# 6_mpu6050.net
KiCad netlist of a schematic drawn in Altium Designer
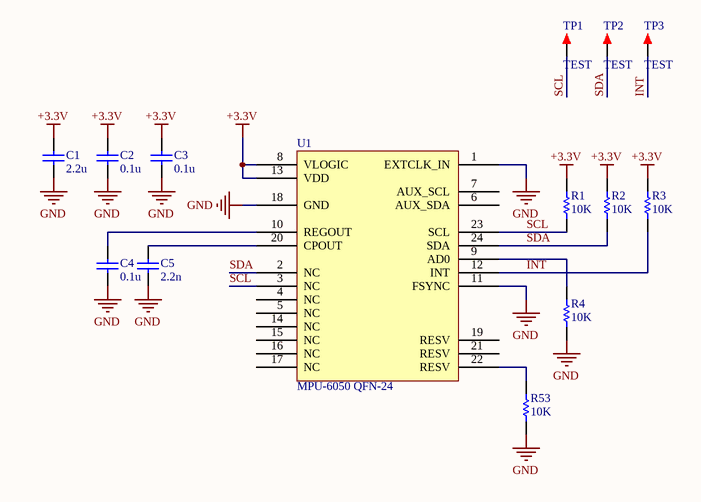
[diagram p0: 6_mpu6050.SchDoc]

(export (version "E")
  (design (tool "Eeschema 10.0.6"))
  (components
    (comp (ref "C1")
      (value "2.2u")
      (footprint "CAP_0603_SMD")
      (description "Capacitor, 0603, SMD")
      (fields (field (name "PUBLISHER") "Altium Limited"))
      (libsource (lib "myRLC") (part "CAP_0603_SMD"))
    )
    (comp (ref "C2")
      (value "0.1u")
      (footprint "CAP_0603_SMD")
      (description "Capacitor, 0603, SMD")
      (fields (field (name "PUBLISHER") "Altium Limited"))
      (libsource (lib "myRLC") (part "CAP_0603_SMD"))
    )
    (comp (ref "C3")
      (value "0.1u")
      (footprint "CAP_0603_SMD")
      (description "Capacitor, 0603, SMD")
      (fields (field (name "PUBLISHER") "Altium Limited"))
      (libsource (lib "myRLC") (part "CAP_0603_SMD"))
    )
    (comp (ref "C4")
      (value "0.1u")
      (footprint "CAP_0603_SMD")
      (description "Capacitor, 0603, SMD")
      (fields (field (name "PUBLISHER") "Altium Limited"))
      (libsource (lib "myRLC") (part "CAP_0603_SMD"))
    )
    (comp (ref "C5")
      (value "2.2n")
      (footprint "CAP_0603_SMD")
      (description "Capacitor, 0603, SMD")
      (fields (field (name "PUBLISHER") "Altium Limited"))
      (libsource (lib "myRLC") (part "CAP_0603_SMD"))
    )
    (comp (ref "R1")
      (value "10K")
      (footprint "RES_0603_SMD")
      (description "Resistor, 0603, SMD")
      (fields (field (name "PUBLISHER") "Altium Limited"))
      (libsource (lib "myRLC") (part "RES_0603_SMD"))
    )
    (comp (ref "R2")
      (value "10K")
      (footprint "RES_0603_SMD")
      (description "Resistor, 0603, SMD")
      (fields (field (name "PUBLISHER") "Altium Limited"))
      (libsource (lib "myRLC") (part "RES_0603_SMD"))
    )
    (comp (ref "R3")
      (value "10K")
      (footprint "RES_0603_SMD")
      (description "Resistor, 0603, SMD")
      (fields (field (name "PUBLISHER") "Altium Limited"))
      (libsource (lib "myRLC") (part "RES_0603_SMD"))
    )
    (comp (ref "R4")
      (value "10K")
      (footprint "RES_0603_SMD")
      (description "Resistor, 0603, SMD")
      (fields (field (name "PUBLISHER") "Altium Limited"))
      (libsource (lib "myRLC") (part "RES_0603_SMD"))
    )
    (comp (ref "R53")
      (value "10K")
      (footprint "RES_0603_SMD")
      (description "Resistor, 0603, SMD")
      (fields (field (name "PUBLISHER") "Altium Limited"))
      (libsource (lib "myRLC") (part "RES_0603_SMD"))
    )
    (comp (ref "TP1")
      (value "TEST")
      (footprint "TEST 1.2")
      (description "测试点")
      (libsource (lib "0.7 - 常用按键-开关-蜂鸣器-电池-测试点") (part "TEST"))
    )
    (comp (ref "TP2")
      (value "TEST")
      (footprint "TEST 1.2")
      (description "测试点")
      (libsource (lib "0.7 - 常用按键-开关-蜂鸣器-电池-测试点") (part "TEST"))
    )
    (comp (ref "TP3")
      (value "TEST")
      (footprint "TEST 1.2")
      (description "测试点")
      (libsource (lib "0.7 - 常用按键-开关-蜂鸣器-电池-测试点") (part "TEST"))
    )
    (comp (ref "U1")
      (value "MPU-6050 QFN-24")
      (footprint "IC_QFN-24_4x4_NoExposedPad")
      (description "Triple Axis Accelerometer and Gyro")
      (libsource (lib "myICs") (part "MPU-6050 QFN24 4x4"))
    )
  )
  (nets
    (net (code "1") (name "+3.3V") (class "Default")
      (node (ref "C1") (pin "2") (pinfunction "2_2") (pintype "passive"))
      (node (ref "C2") (pin "2") (pinfunction "2_2") (pintype "passive"))
      (node (ref "C3") (pin "2") (pinfunction "2_2") (pintype "passive"))
      (node (ref "R1") (pin "2") (pinfunction "2_2") (pintype "passive"))
      (node (ref "R2") (pin "2") (pinfunction "2_2") (pintype "passive"))
      (node (ref "R3") (pin "2") (pinfunction "2_2") (pintype "passive"))
      (node (ref "U1") (pin "13") (pinfunction "VDD_13") (pintype "passive"))
      (node (ref "U1") (pin "8") (pinfunction "VLOGIC_8") (pintype "passive"))
    )
    (net (code "2") (name "/INT") (class "Default")
      (node (ref "R3") (pin "1") (pinfunction "1_1") (pintype "passive"))
      (node (ref "TP3") (pin "1") (pinfunction "1_1") (pintype "passive"))
      (node (ref "U1") (pin "12") (pinfunction "INT_12") (pintype "passive"))
    )
    (net (code "3") (name "/SCL") (class "Default")
      (node (ref "R1") (pin "1") (pinfunction "1_1") (pintype "passive"))
      (node (ref "TP1") (pin "1") (pinfunction "1_1") (pintype "passive"))
      (node (ref "U1") (pin "23") (pinfunction "SCL_23") (pintype "passive"))
      (node (ref "U1") (pin "3") (pinfunction "NC_3") (pintype "passive"))
    )
    (net (code "4") (name "/SDA") (class "Default")
      (node (ref "R2") (pin "1") (pinfunction "1_1") (pintype "passive"))
      (node (ref "TP2") (pin "1") (pinfunction "1_1") (pintype "passive"))
      (node (ref "U1") (pin "2") (pinfunction "NC_2") (pintype "passive"))
      (node (ref "U1") (pin "24") (pinfunction "SDA_24") (pintype "passive"))
    )
    (net (code "5") (name "GND") (class "Default")
      (node (ref "C1") (pin "1") (pinfunction "1_1") (pintype "passive"))
      (node (ref "C2") (pin "1") (pinfunction "1_1") (pintype "passive"))
      (node (ref "C3") (pin "1") (pinfunction "1_1") (pintype "passive"))
      (node (ref "C4") (pin "2") (pinfunction "2_2") (pintype "passive"))
      (node (ref "C5") (pin "2") (pinfunction "2_2") (pintype "passive"))
      (node (ref "R4") (pin "1") (pinfunction "1_1") (pintype "passive"))
      (node (ref "R53") (pin "1") (pinfunction "1_1") (pintype "passive"))
      (node (ref "U1") (pin "1") (pinfunction "EXTCLK_IN_1") (pintype "passive"))
      (node (ref "U1") (pin "11") (pinfunction "FSYNC_11") (pintype "passive"))
      (node (ref "U1") (pin "18") (pinfunction "GND_18") (pintype "passive"))
    )
    (net (code "6") (name "Net-(R53-Pad2)") (class "Default")
      (node (ref "R53") (pin "2") (pinfunction "2_2") (pintype "passive"))
      (node (ref "U1") (pin "22") (pinfunction "RESV_22") (pintype "passive"))
    )
    (net (code "7") (name "Net-(U1-AD0)") (class "Default")
      (node (ref "R4") (pin "2") (pinfunction "2_2") (pintype "passive"))
      (node (ref "U1") (pin "9") (pinfunction "AD0_9") (pintype "passive"))
    )
    (net (code "8") (name "Net-(U1-CPOUT)") (class "Default")
      (node (ref "C5") (pin "1") (pinfunction "1_1") (pintype "passive"))
      (node (ref "U1") (pin "20") (pinfunction "CPOUT_20") (pintype "passive"))
    )
    (net (code "9") (name "Net-(U1-REGOUT)") (class "Default")
      (node (ref "C4") (pin "1") (pinfunction "1_1") (pintype "passive"))
      (node (ref "U1") (pin "10") (pinfunction "REGOUT_10") (pintype "passive"))
    )
    (net (code "10") (name "unconnected-(U1-AUX_SCL-Pad7)") (class "Default")
      (node (ref "U1") (pin "7") (pinfunction "AUX_SCL_7") (pintype "passive"))
    )
    (net (code "11") (name "unconnected-(U1-AUX_SDA-Pad6)") (class "Default")
      (node (ref "U1") (pin "6") (pinfunction "AUX_SDA_6") (pintype "passive"))
    )
    (net (code "12") (name "unconnected-(U1-NC-Pad4)") (class "Default")
      (node (ref "U1") (pin "4") (pinfunction "NC_4") (pintype "passive"))
    )
    (net (code "13") (name "unconnected-(U1-NC-Pad5)") (class "Default")
      (node (ref "U1") (pin "5") (pinfunction "NC_5") (pintype "passive"))
    )
    (net (code "14") (name "unconnected-(U1-NC-Pad14)") (class "Default")
      (node (ref "U1") (pin "14") (pinfunction "NC_14") (pintype "passive"))
    )
    (net (code "15") (name "unconnected-(U1-NC-Pad15)") (class "Default")
      (node (ref "U1") (pin "15") (pinfunction "NC_15") (pintype "passive"))
    )
    (net (code "16") (name "unconnected-(U1-NC-Pad16)") (class "Default")
      (node (ref "U1") (pin "16") (pinfunction "NC_16") (pintype "passive"))
    )
    (net (code "17") (name "unconnected-(U1-NC-Pad17)") (class "Default")
      (node (ref "U1") (pin "17") (pinfunction "NC_17") (pintype "passive"))
    )
    (net (code "18") (name "unconnected-(U1-RESV-Pad19)") (class "Default")
      (node (ref "U1") (pin "19") (pinfunction "RESV_19") (pintype "passive"))
    )
    (net (code "19") (name "unconnected-(U1-RESV-Pad21)") (class "Default")
      (node (ref "U1") (pin "21") (pinfunction "RESV_21") (pintype "passive"))
    )
  )
)
